# SparkFun_ZED-F9R_v11.net
KiCad netlist of a schematic drawn in EAGLE
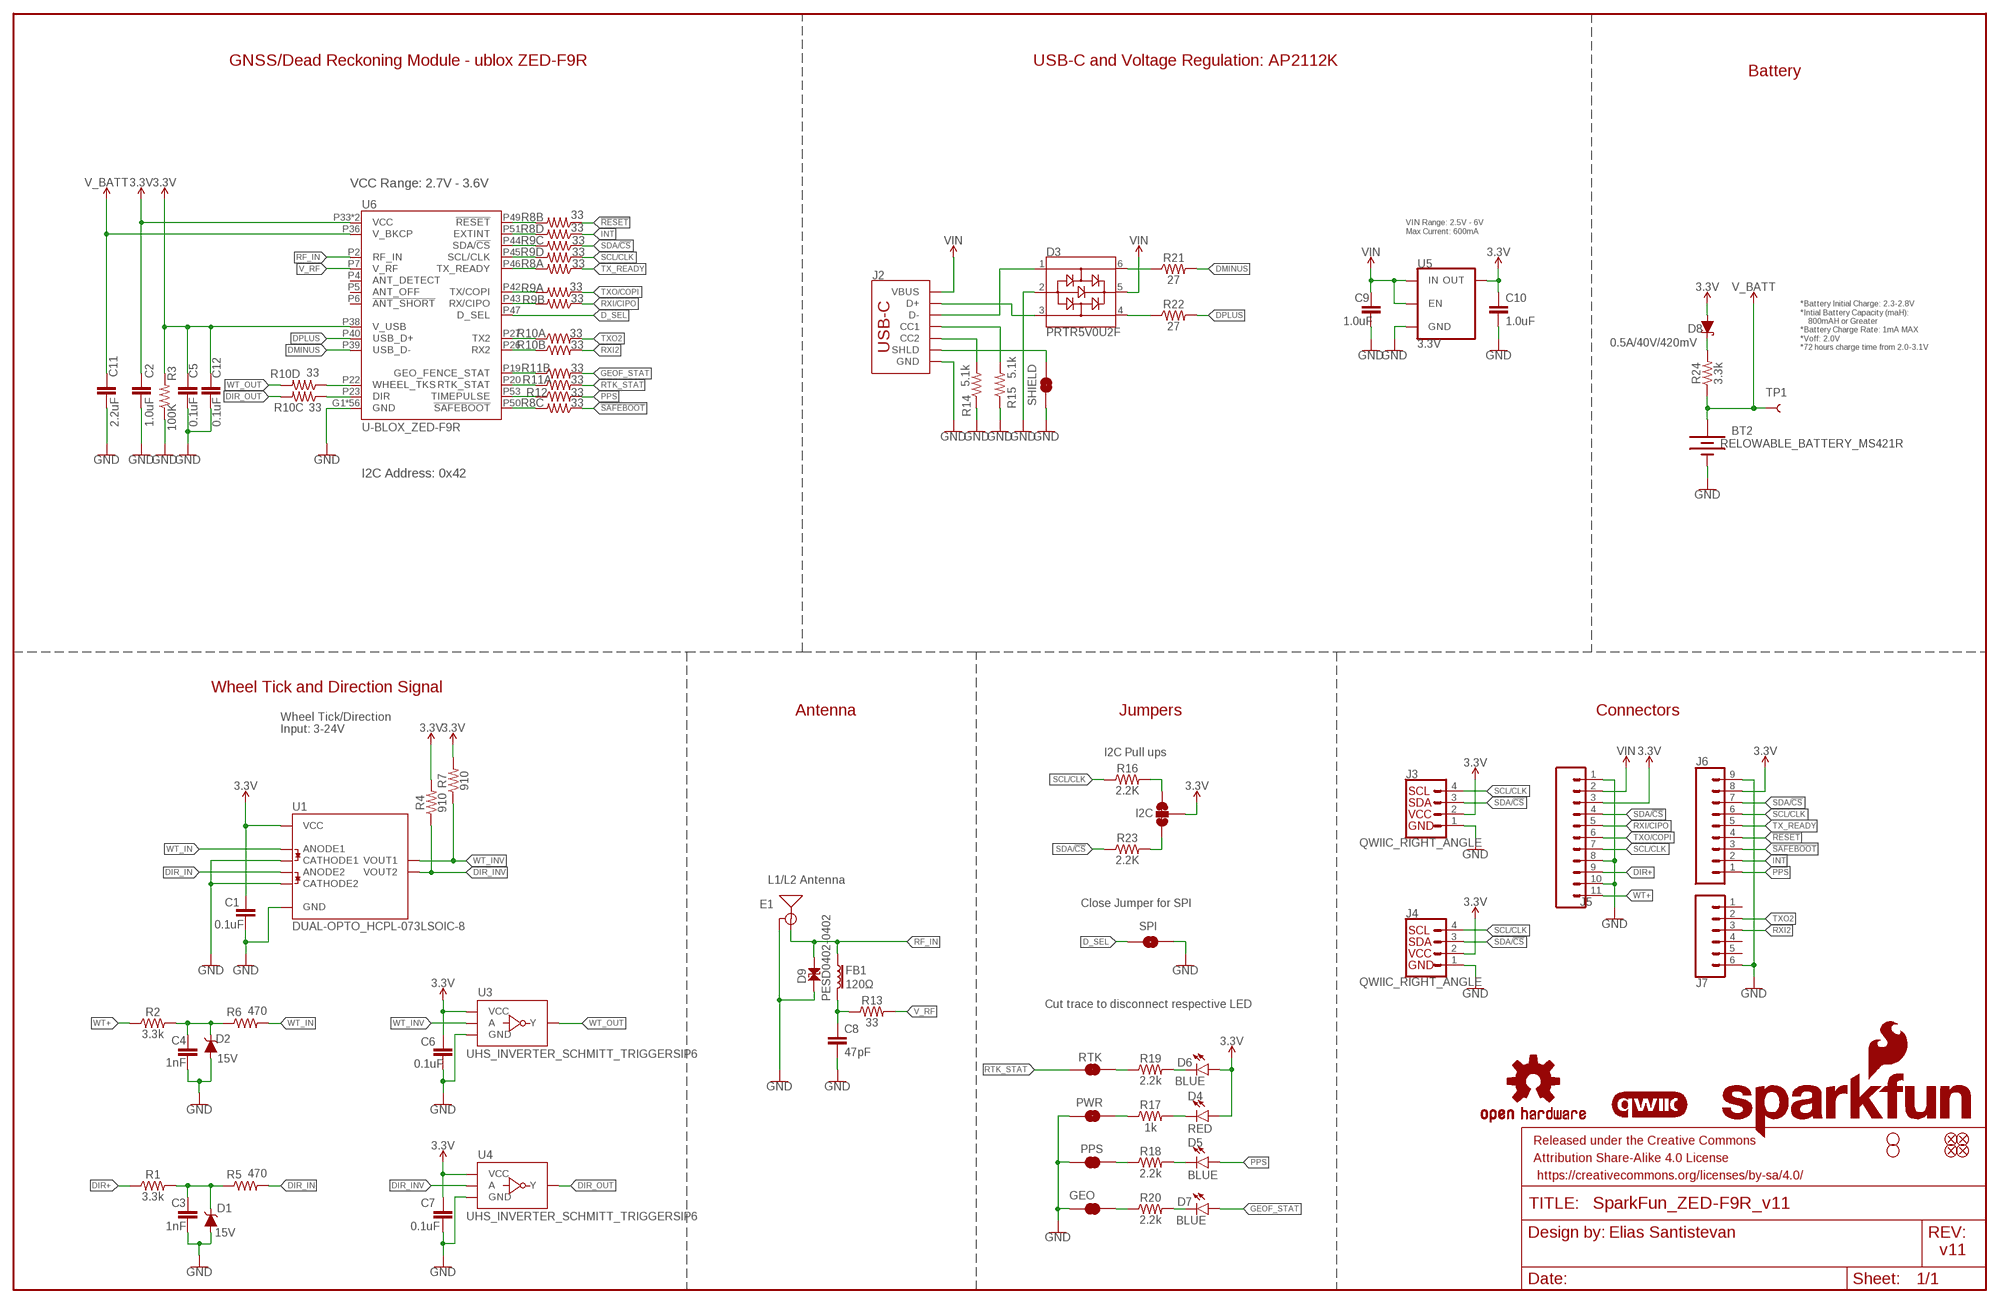
[diagram p0: schematic, sheet 1]

(export (version "E")
  (design (tool "Eeschema 10.0.6"))
  (components
    (comp (ref "$1_25_$_2020-03-30_22-52-05")
      (value "STAND-OFFTIGHT")
      (footprint "eagle-import:STAND-OFF-TIGHT")
      (libsource (lib "eagle-import") (part "STAND-OFFTIGHT"))
    )
    (comp (ref "BT2")
      (value "RELOWABLE_BATTERY_MS421R")
      (footprint "eagle-import:MS421R_IV03E")
      (libsource (lib "eagle-import") (part "RELOWABLE_BATTERY_MS421R"))
    )
    (comp (ref "C1")
      (value "0.1uF")
      (footprint "eagle-import:0402-TIGHT")
      (libsource (lib "eagle-import") (part "0.1UF-0402T-6.3V-10%-X7R"))
    )
    (comp (ref "C2")
      (value "1.0uF")
      (footprint "eagle-import:0402-TIGHT")
      (libsource (lib "eagle-import") (part "1.0UF-0402T-16V-10%"))
    )
    (comp (ref "C3")
      (value "1nF")
      (footprint "eagle-import:0402")
      (libsource (lib "eagle-import") (part "1.0NF/1000PF-0402-25V-10%-X7R"))
    )
    (comp (ref "C4")
      (value "1nF")
      (footprint "eagle-import:0402")
      (libsource (lib "eagle-import") (part "1.0NF/1000PF-0402-25V-10%-X7R"))
    )
    (comp (ref "C5")
      (value "0.1uF")
      (footprint "eagle-import:0402-TIGHT")
      (libsource (lib "eagle-import") (part "0.1UF-0402T-6.3V-10%-X7R"))
    )
    (comp (ref "C6")
      (value "0.1uF")
      (footprint "eagle-import:0402-TIGHT")
      (libsource (lib "eagle-import") (part "0.1UF-0402T-6.3V-10%-X7R"))
    )
    (comp (ref "C7")
      (value "0.1uF")
      (footprint "eagle-import:0402-TIGHT")
      (libsource (lib "eagle-import") (part "0.1UF-0402T-6.3V-10%-X7R"))
    )
    (comp (ref "C8")
      (value "47pF")
      (footprint "eagle-import:0402")
      (libsource (lib "eagle-import") (part "47PF-0402-25V-5%-X7R"))
    )
    (comp (ref "C9")
      (value "1.0uF")
      (footprint "eagle-import:0402-TIGHT")
      (libsource (lib "eagle-import") (part "1.0UF-0402T-16V-10%"))
    )
    (comp (ref "C10")
      (value "1.0uF")
      (footprint "eagle-import:0402-TIGHT")
      (libsource (lib "eagle-import") (part "1.0UF-0402T-16V-10%"))
    )
    (comp (ref "C11")
      (value "2.2uF")
      (footprint "eagle-import:0402-TIGHT")
      (libsource (lib "eagle-import") (part "2.2UF-0402_TIGHT-10V-10%-X5R"))
    )
    (comp (ref "C12")
      (value "0.1uF")
      (footprint "eagle-import:0402-TIGHT")
      (libsource (lib "eagle-import") (part "0.1UF-0402T-6.3V-10%-X7R"))
    )
    (comp (ref "D1")
      (value "15V")
      (footprint "eagle-import:SOT23-3")
      (libsource (lib "eagle-import") (part "DIODE-ZENER-BZX84C15LT3G"))
    )
    (comp (ref "D2")
      (value "15V")
      (footprint "eagle-import:SOT23-3")
      (libsource (lib "eagle-import") (part "DIODE-ZENER-BZX84C15LT3G"))
    )
    (comp (ref "D3")
      (value "PRTR5V0U2F")
      (footprint "eagle-import:SOT886")
      (libsource (lib "eagle-import") (part "PRTR5V0U2F"))
    )
    (comp (ref "D4")
      (value "RED")
      (footprint "eagle-import:LED-0603")
      (libsource (lib "eagle-import") (part "LED-RED0603"))
    )
    (comp (ref "D5")
      (value "BLUE")
      (footprint "eagle-import:LED-0603")
      (libsource (lib "eagle-import") (part "LED-BLUE0603"))
    )
    (comp (ref "D6")
      (value "BLUE")
      (footprint "eagle-import:LED-0603")
      (libsource (lib "eagle-import") (part "LED-BLUE0603"))
    )
    (comp (ref "D7")
      (value "BLUE")
      (footprint "eagle-import:LED-0603")
      (libsource (lib "eagle-import") (part "LED-BLUE0603"))
    )
    (comp (ref "D8")
      (value "0.5A/40V/420mV")
      (footprint "eagle-import:SOD-323")
      (libsource (lib "eagle-import") (part "DIODE-SCHOTTKY-PMEG4005EJ"))
    )
    (comp (ref "D9")
      (value "PESD0402-0402")
      (footprint "eagle-import:0402")
      (fields
        (field (name "DIGIKEY_PART") "PESD0402-140CT-ND")
        (field (name "MOUSE_PART") "650-PESD0402-140")
      )
      (libsource (lib "eagle-import") (part "PESD0402-0402"))
    )
    (comp (ref "E1")
      (value "ANTENNA-SMA-GROUNDEDEDGE_SMA")
      (footprint "eagle-import:SMA-EDGE")
      (libsource (lib "eagle-import") (part "ANTENNA-SMA-GROUNDEDEDGE_SMA"))
    )
    (comp (ref "FB1")
      (value "120Ω")
      (footprint "eagle-import:0402")
      (fields (field (name "MFG_PART") "BLM15HB121SN1D"))
      (libsource (lib "eagle-import") (part "FERRITE_BEAD-120_OHM-0402"))
    )
    (comp (ref "FD1")
      (value "FIDUCIALUFIDUCIAL")
      (footprint "eagle-import:FIDUCIAL-MICRO")
      (libsource (lib "eagle-import") (part "FIDUCIALUFIDUCIAL"))
    )
    (comp (ref "FD2")
      (value "FIDUCIALUFIDUCIAL")
      (footprint "eagle-import:FIDUCIAL-MICRO")
      (libsource (lib "eagle-import") (part "FIDUCIALUFIDUCIAL"))
    )
    (comp (ref "FD3")
      (value "FIDUCIALUFIDUCIAL")
      (footprint "eagle-import:FIDUCIAL-MICRO")
      (libsource (lib "eagle-import") (part "FIDUCIALUFIDUCIAL"))
    )
    (comp (ref "FD4")
      (value "FIDUCIALUFIDUCIAL")
      (footprint "eagle-import:FIDUCIAL-MICRO")
      (libsource (lib "eagle-import") (part "FIDUCIALUFIDUCIAL"))
    )
    (comp (ref "FRAME1")
      (value "FRAME-LEDGER")
      (footprint "eagle-import:CREATIVE_COMMONS")
      (libsource (lib "eagle-import") (part "FRAME-LEDGER"))
    )
    (comp (ref "GEO")
      (value "JUMPER-SMT_2_NC_TRACE_SILK")
      (footprint "eagle-import:SMT-JUMPER_2_NC_TRACE_SILK")
      (libsource (lib "eagle-import") (part "JUMPER-SMT_2_NC_TRACE_SILK"))
    )
    (comp (ref "H2")
      (value "STAND-OFFTIGHT")
      (footprint "eagle-import:STAND-OFF-TIGHT")
      (libsource (lib "eagle-import") (part "STAND-OFFTIGHT"))
    )
    (comp (ref "I2C")
      (value "JUMPER-SMT_3_2-NC_TRACE_SILK")
      (footprint "eagle-import:SMT-JUMPER_3_2-NC_TRACE_SILK")
      (libsource (lib "eagle-import") (part "JUMPER-SMT_3_2-NC_TRACE_SILK"))
    )
    (comp (ref "J2")
      (value "USB_C_2-LAYER_PADS")
      (footprint "eagle-import:USB-C-16P-2LAYER-PADS")
      (libsource (lib "eagle-import") (part "USB_C_2-LAYER_PADS"))
    )
    (comp (ref "J3")
      (value "QWIIC_RIGHT_ANGLE")
      (footprint "eagle-import:JST04_1MM_RA")
      (libsource (lib "eagle-import") (part "QWIIC_CONNECTORJS-1MM"))
    )
    (comp (ref "J4")
      (value "QWIIC_RIGHT_ANGLE")
      (footprint "eagle-import:JST04_1MM_RA")
      (libsource (lib "eagle-import") (part "QWIIC_CONNECTORJS-1MM"))
    )
    (comp (ref "J5")
      (value "CONN_111X11_NO_SILK")
      (footprint "eagle-import:1X11_NO_SILK")
      (libsource (lib "eagle-import") (part "CONN_111X11_NO_SILK"))
    )
    (comp (ref "J6")
      (value "CONN_09NO_SILK")
      (footprint "eagle-import:1X09_NO_SILK")
      (libsource (lib "eagle-import") (part "CONN_09NO_SILK"))
    )
    (comp (ref "J7")
      (value "CONN_06NO_SILK_NO_POP")
      (footprint "eagle-import:1X06_NO_SILK")
      (libsource (lib "eagle-import") (part "CONN_06NO_SILK_NO_POP"))
    )
    (comp (ref "LOGO1")
      (value "OSHW-LOGOS")
      (footprint "eagle-import:OSHW-LOGO-S")
      (libsource (lib "eagle-import") (part "OSHW-LOGOS"))
    )
    (comp (ref "LOGO2")
      (value "QWIIC_LOGO_4MM")
      (footprint "eagle-import:QWIIC_4MM")
      (libsource (lib "eagle-import") (part "QWIIC_LOGO_4MM"))
    )
    (comp (ref "LOGO3")
      (value "SFE_LOGO_NAME_FLAME.2_INCH")
      (footprint "eagle-import:SFE_LOGO_NAME_FLAME_.2")
      (libsource (lib "eagle-import") (part "SFE_LOGO_NAME_FLAME.2_INCH"))
    )
    (comp (ref "PPS")
      (value "JUMPER-SMT_2_NC_TRACE_SILK")
      (footprint "eagle-import:SMT-JUMPER_2_NC_TRACE_SILK")
      (libsource (lib "eagle-import") (part "JUMPER-SMT_2_NC_TRACE_SILK"))
    )
    (comp (ref "PWR")
      (value "JUMPER-SMT_2_NC_TRACE_SILK")
      (footprint "eagle-import:SMT-JUMPER_2_NC_TRACE_SILK")
      (libsource (lib "eagle-import") (part "JUMPER-SMT_2_NC_TRACE_SILK"))
    )
    (comp (ref "R1")
      (value "3.3k")
      (footprint "eagle-import:0603")
      (libsource (lib "eagle-import") (part "3.3KOHM-0603-1/10W-1%"))
    )
    (comp (ref "R2")
      (value "3.3k")
      (footprint "eagle-import:0603")
      (libsource (lib "eagle-import") (part "3.3KOHM-0603-1/10W-1%"))
    )
    (comp (ref "R3")
      (value "100K")
      (footprint "eagle-import:0402")
      (libsource (lib "eagle-import") (part "100KOHM-0402-1/16W-1%"))
    )
    (comp (ref "R4")
      (value "910")
      (footprint "eagle-import:0603")
      (libsource (lib "eagle-import") (part "910OHM-0603-1/10W-5%"))
    )
    (comp (ref "R5")
      (value "470")
      (footprint "eagle-import:0603")
      (libsource (lib "eagle-import") (part "470OHM-0603-1/10W-1%"))
    )
    (comp (ref "R6")
      (value "470")
      (footprint "eagle-import:0603")
      (libsource (lib "eagle-import") (part "470OHM-0603-1/10W-1%"))
    )
    (comp (ref "R7")
      (value "910")
      (footprint "eagle-import:0603")
      (libsource (lib "eagle-import") (part "910OHM-0603-1/10W-5%"))
    )
    (comp (ref "R8")
      (value "33")
      (footprint "eagle-import:1206_RA")
      (libsource (lib "eagle-import") (part "33OHM_RA-1206-1/16W-5%"))
    )
    (comp (ref "R9")
      (value "33")
      (footprint "eagle-import:1206_RA")
      (libsource (lib "eagle-import") (part "33OHM_RA-1206-1/16W-5%"))
    )
    (comp (ref "R10")
      (value "33")
      (footprint "eagle-import:1206_RA")
      (libsource (lib "eagle-import") (part "33OHM_RA-1206-1/16W-5%"))
    )
    (comp (ref "R11")
      (value "33")
      (footprint "eagle-import:1206_RA")
      (libsource (lib "eagle-import") (part "33OHM_RA-1206-1/16W-5%"))
    )
    (comp (ref "R12")
      (value "33")
      (footprint "eagle-import:0603")
      (libsource (lib "eagle-import") (part "33OHM-0603-1/10W-1%"))
    )
    (comp (ref "R13")
      (value "33")
      (footprint "eagle-import:0603")
      (libsource (lib "eagle-import") (part "33OHM-0603-1/10W-1%"))
    )
    (comp (ref "R14")
      (value "5.1k")
      (footprint "eagle-import:0402")
      (libsource (lib "eagle-import") (part "5.1KOHM-0402-1/16W-1%"))
    )
    (comp (ref "R15")
      (value "5.1k")
      (footprint "eagle-import:0402")
      (libsource (lib "eagle-import") (part "5.1KOHM-0402-1/16W-1%"))
    )
    (comp (ref "R16")
      (value "2.2K")
      (footprint "eagle-import:0402")
      (libsource (lib "eagle-import") (part "2.2KOHM-0402-1/16W-1%"))
    )
    (comp (ref "R17")
      (value "1KOHM-0402-1/16W-1%")
      (footprint "eagle-import:0402")
      (libsource (lib "eagle-import") (part "1KOHM-0402-1/16W-1%"))
    )
    (comp (ref "R18")
      (value "2.2k")
      (footprint "eagle-import:0603")
      (libsource (lib "eagle-import") (part "2.2KOHM-0603-1/10W-1%"))
    )
    (comp (ref "R19")
      (value "2.2k")
      (footprint "eagle-import:0603")
      (libsource (lib "eagle-import") (part "2.2KOHM-0603-1/10W-1%"))
    )
    (comp (ref "R20")
      (value "2.2k")
      (footprint "eagle-import:0603")
      (libsource (lib "eagle-import") (part "2.2KOHM-0603-1/10W-1%"))
    )
    (comp (ref "R21")
      (value "27")
      (footprint "eagle-import:0603")
      (libsource (lib "eagle-import") (part "27OHM-0603-1/10W-1%"))
    )
    (comp (ref "R22")
      (value "27")
      (footprint "eagle-import:0603")
      (libsource (lib "eagle-import") (part "27OHM-0603-1/10W-1%"))
    )
    (comp (ref "R23")
      (value "2.2K")
      (footprint "eagle-import:0402")
      (libsource (lib "eagle-import") (part "2.2KOHM-0402-1/16W-1%"))
    )
    (comp (ref "R24")
      (value "3.3k")
      (footprint "eagle-import:0603")
      (libsource (lib "eagle-import") (part "3.3KOHM-0603-1/10W-1%"))
    )
    (comp (ref "RTK")
      (value "JUMPER-SMT_2_NC_TRACE_SILK")
      (footprint "eagle-import:SMT-JUMPER_2_NC_TRACE_SILK")
      (libsource (lib "eagle-import") (part "JUMPER-SMT_2_NC_TRACE_SILK"))
    )
    (comp (ref "SHIELD")
      (value "JUMPER-SMT_2_NC_TRACE_SILK")
      (footprint "eagle-import:SMT-JUMPER_2_NC_TRACE_SILK")
      (libsource (lib "eagle-import") (part "JUMPER-SMT_2_NC_TRACE_SILK"))
    )
    (comp (ref "SPI")
      (value "JUMPER-SMT_2_NO_SILK")
      (footprint "eagle-import:SMT-JUMPER_2_NO_SILK")
      (libsource (lib "eagle-import") (part "JUMPER-SMT_2_NO_SILK"))
    )
    (comp (ref "TP1")
      (value "TEST-POINT3X5")
      (footprint "eagle-import:PAD.03X.05")
      (libsource (lib "eagle-import") (part "TEST-POINT3X5"))
    )
    (comp (ref "U1")
      (value "DUAL-OPTO_HCPL-073LSOIC-8")
      (footprint "eagle-import:SO08")
      (libsource (lib "eagle-import") (part "DUAL-OPTO_HCPL-073LSOIC-8"))
    )
    (comp (ref "U3")
      (value "UHS_INVERTER_SCHMITT_TRIGGERSIP6")
      (footprint "eagle-import:SIP6_MICROPAK2")
      (libsource (lib "eagle-import") (part "UHS_INVERTER_SCHMITT_TRIGGER_MPAK2"))
    )
    (comp (ref "U4")
      (value "UHS_INVERTER_SCHMITT_TRIGGERSIP6")
      (footprint "eagle-import:SIP6_MICROPAK2")
      (libsource (lib "eagle-import") (part "UHS_INVERTER_SCHMITT_TRIGGER_MPAK2"))
    )
    (comp (ref "U5")
      (value "3.3V")
      (footprint "eagle-import:SOT23-5")
      (libsource (lib "eagle-import") (part "V_REG_AP2112K-3.3V"))
    )
    (comp (ref "U6")
      (value "U-BLOX_ZED-F9R")
      (footprint "eagle-import:UBLOX_ZED_F9R")
      (libsource (lib "eagle-import") (part "U-BLOX_ZED-F9R"))
    )
  )
  (nets
    (net (code "1") (name "/SDA{slash}~{CS}") (class "Default")
      (node (ref "J3") (pin "3") (pinfunction "3_3") (pintype "passive"))
      (node (ref "J4") (pin "3") (pinfunction "3_3") (pintype "passive"))
      (node (ref "J5") (pin "4") (pinfunction "4_4") (pintype "passive"))
      (node (ref "J6") (pin "7") (pinfunction "7_7") (pintype "passive"))
      (node (ref "R23") (pin "1") (pinfunction "1_1") (pintype "passive"))
      (node (ref "R9") (pin "P3") (pinfunction "1_P3") (pintype "passive"))
    )
    (net (code "2") (name "/~{RESET}") (class "Default")
      (node (ref "J6") (pin "4") (pinfunction "4_4") (pintype "passive"))
      (node (ref "R8") (pin "P2") (pinfunction "1_P2") (pintype "passive"))
    )
    (net (code "3") (name "/~{SAFEBOOT}") (class "Default")
      (node (ref "J6") (pin "3") (pinfunction "3_3") (pintype "passive"))
      (node (ref "R8") (pin "P3") (pinfunction "1_P3") (pintype "passive"))
    )
    (net (code "4") (name "3.3V") (class "Default")
      (node (ref "C1") (pin "1") (pinfunction "1_1") (pintype "passive"))
      (node (ref "C10") (pin "1") (pinfunction "1_1") (pintype "passive"))
      (node (ref "C12") (pin "1") (pinfunction "1_1") (pintype "passive"))
      (node (ref "C2") (pin "1") (pinfunction "1_1") (pintype "passive"))
      (node (ref "C5") (pin "1") (pinfunction "1_1") (pintype "passive"))
      (node (ref "C6") (pin "1") (pinfunction "1_1") (pintype "passive"))
      (node (ref "C7") (pin "1") (pinfunction "1_1") (pintype "passive"))
      (node (ref "D4") (pin "A") (pinfunction "A_A") (pintype "passive"))
      (node (ref "D6") (pin "A") (pinfunction "A_A") (pintype "passive"))
      (node (ref "D8") (pin "A") (pinfunction "A_A") (pintype "passive"))
      (node (ref "I2C") (pin "2") (pinfunction "2_2") (pintype "passive"))
      (node (ref "J3") (pin "2") (pinfunction "2_2") (pintype "power_in"))
      (node (ref "J4") (pin "2") (pinfunction "2_2") (pintype "power_in"))
      (node (ref "J5") (pin "3") (pinfunction "3_3") (pintype "passive"))
      (node (ref "J6") (pin "8") (pinfunction "8_8") (pintype "passive"))
      (node (ref "R3") (pin "2") (pinfunction "2_2") (pintype "passive"))
      (node (ref "R4") (pin "2") (pinfunction "2_2") (pintype "passive"))
      (node (ref "R7") (pin "2") (pinfunction "2_2") (pintype "passive"))
      (node (ref "U1") (pin "8") (pinfunction "VCC_8") (pintype "power_in"))
      (node (ref "U3") (pin "P6") (pinfunction "VCC_P6") (pintype "power_in"))
      (node (ref "U4") (pin "P6") (pinfunction "VCC_P6") (pintype "power_in"))
      (node (ref "U5") (pin "5") (pinfunction "OUT_5") (pintype "passive"))
      (node (ref "U6") (pin "P33") (pinfunction "VCC_P33") (pintype "power_in"))
      (node (ref "U6") (pin "P34") (pinfunction "VCC_P34") (pintype "power_in"))
      (node (ref "U6") (pin "P38") (pinfunction "V_USB_P38") (pintype "power_in"))
    )
    (net (code "5") (name "DIR+") (class "Default")
      (node (ref "J5") (pin "9") (pinfunction "9_9") (pintype "passive"))
      (node (ref "R1") (pin "1") (pinfunction "1_1") (pintype "passive"))
    )
    (net (code "6") (name "DIR_IN") (class "Default")
      (node (ref "R5") (pin "2") (pinfunction "2_2") (pintype "passive"))
      (node (ref "U1") (pin "4") (pinfunction "ANODE2_4") (pintype "input"))
    )
    (net (code "7") (name "DIR_INV") (class "Default")
      (node (ref "R4") (pin "1") (pinfunction "1_1") (pintype "passive"))
      (node (ref "U1") (pin "6") (pinfunction "VOUT2_6") (pintype "output"))
      (node (ref "U4") (pin "P2") (pinfunction "A_P2") (pintype "input"))
    )
    (net (code "8") (name "DIR_OUT") (class "Default")
      (node (ref "R10") (pin "P6") (pinfunction "2_P6") (pintype "passive"))
      (node (ref "U4") (pin "P4") (pinfunction "Y_P4") (pintype "output"))
    )
    (net (code "9") (name "DMINUS") (class "Default")
      (node (ref "R21") (pin "2") (pinfunction "2_2") (pintype "passive"))
      (node (ref "U6") (pin "P39") (pinfunction "USB_D-_P39") (pintype "bidirectional"))
    )
    (net (code "10") (name "DPLUS") (class "Default")
      (node (ref "R22") (pin "2") (pinfunction "2_2") (pintype "passive"))
      (node (ref "U6") (pin "P40") (pinfunction "USB_D+_P40") (pintype "bidirectional"))
    )
    (net (code "11") (name "D_SEL") (class "Default")
      (node (ref "SPI") (pin "1") (pinfunction "1_1") (pintype "passive"))
      (node (ref "U6") (pin "P47") (pinfunction "D_SEL_P47") (pintype "bidirectional"))
    )
    (net (code "12") (name "GEOF_STAT") (class "Default")
      (node (ref "D7") (pin "A") (pinfunction "A_A") (pintype "passive"))
      (node (ref "R11") (pin "P7") (pinfunction "2_P7") (pintype "passive"))
    )
    (net (code "13") (name "GND") (class "Default")
      (node (ref "BT2") (pin "-") (pinfunction "-_-") (pintype "power_in"))
      (node (ref "C1") (pin "2") (pinfunction "2_2") (pintype "passive"))
      (node (ref "C10") (pin "2") (pinfunction "2_2") (pintype "passive"))
      (node (ref "C11") (pin "2") (pinfunction "2_2") (pintype "passive"))
      (node (ref "C12") (pin "2") (pinfunction "2_2") (pintype "passive"))
      (node (ref "C2") (pin "2") (pinfunction "2_2") (pintype "passive"))
      (node (ref "C3") (pin "2") (pinfunction "2_2") (pintype "passive"))
      (node (ref "C4") (pin "2") (pinfunction "2_2") (pintype "passive"))
      (node (ref "C5") (pin "2") (pinfunction "2_2") (pintype "passive"))
      (node (ref "C6") (pin "2") (pinfunction "2_2") (pintype "passive"))
      (node (ref "C7") (pin "2") (pinfunction "2_2") (pintype "passive"))
      (node (ref "C8") (pin "2") (pinfunction "2_2") (pintype "passive"))
      (node (ref "C9") (pin "2") (pinfunction "2_2") (pintype "passive"))
      (node (ref "D1") (pin "1") (pinfunction "A_1") (pintype "passive"))
      (node (ref "D2") (pin "1") (pinfunction "A_1") (pintype "passive"))
      (node (ref "D3") (pin "2") (pinfunction "2_2") (pintype "power_in"))
      (node (ref "D9") (pin "1") (pinfunction "1_1") (pintype "bidirectional"))
      (node (ref "E1") (pin "GND@0") (pinfunction "GND_GND@0") (pintype "bidirectional"))
      (node (ref "E1") (pin "GND@1") (pinfunction "GND_GND@1") (pintype "bidirectional"))
      (node (ref "E1") (pin "GND@2") (pinfunction "GND_GND@2") (pintype "bidirectional"))
      (node (ref "E1") (pin "GND@3") (pinfunction "GND_GND@3") (pintype "bidirectional"))
      (node (ref "GEO") (pin "1") (pinfunction "1_1") (pintype "passive"))
      (node (ref "J2") (pin "GND") (pinfunction "GND_GND") (pintype "bidirectional"))
      (node (ref "J2") (pin "GND2") (pinfunction "GND_GND2") (pintype "bidirectional"))
      (node (ref "J3") (pin "1") (pinfunction "1_1") (pintype "power_in"))
      (node (ref "J4") (pin "1") (pinfunction "1_1") (pintype "power_in"))
      (node (ref "J5") (pin "1") (pinfunction "1_1") (pintype "passive"))
      (node (ref "J5") (pin "10") (pinfunction "10_10") (pintype "passive"))
      (node (ref "J5") (pin "8") (pinfunction "8_8") (pintype "passive"))
      (node (ref "J6") (pin "9") (pinfunction "9_9") (pintype "passive"))
      (node (ref "J7") (pin "6") (pinfunction "6_6") (pintype "passive"))
      (node (ref "PPS") (pin "1") (pinfunction "1_1") (pintype "passive"))
      (node (ref "PWR") (pin "1") (pinfunction "1_1") (pintype "passive"))
      (node (ref "R14") (pin "1") (pinfunction "1_1") (pintype "passive"))
      (node (ref "R15") (pin "1") (pinfunction "1_1") (pintype "passive"))
      (node (ref "R3") (pin "1") (pinfunction "1_1") (pintype "passive"))
      (node (ref "SHIELD") (pin "1") (pinfunction "1_1") (pintype "passive"))
      (node (ref "SPI") (pin "2") (pinfunction "2_2") (pintype "passive"))
      (node (ref "U1") (pin "2") (pinfunction "CATHODE1_2") (pintype "input"))
      (node (ref "U1") (pin "3") (pinfunction "CATHODE2_3") (pintype "input"))
      (node (ref "U1") (pin "5") (pinfunction "GND_5") (pintype "power_in"))
      (node (ref "U3") (pin "P3") (pinfunction "GND_P3") (pintype "power_in"))
      (node (ref "U4") (pin "P3") (pinfunction "GND_P3") (pintype "power_in"))
      (node (ref "U5") (pin "2") (pinfunction "GND_2") (pintype "input"))
      (node (ref "U6") (pin "G1") (pinfunction "GND_G1") (pintype "power_in"))
      (node (ref "U6") (pin "G10") (pinfunction "GND_G10") (pintype "power_in"))
      (node (ref "U6") (pin "G11") (pinfunction "GND_G11") (pintype "power_in"))
      (node (ref "U6") (pin "G12") (pinfunction "GND_G12") (pintype "power_in"))
      (node (ref "U6") (pin "G13") (pinfunction "GND_G13") (pintype "power_in"))
      (node (ref "U6") (pin "G14") (pinfunction "GND_G14") (pintype "power_in"))
      (node (ref "U6") (pin "G15") (pinfunction "GND_G15") (pintype "power_in"))
      (node (ref "U6") (pin "G16") (pinfunction "GND_G16") (pintype "power_in"))
      (node (ref "U6") (pin "G17") (pinfunction "GND_G17") (pintype "power_in"))
      (node (ref "U6") (pin "G18") (pinfunction "GND_G18") (pintype "power_in"))
      (node (ref "U6") (pin "G19") (pinfunction "GND_G19") (pintype "power_in"))
      (node (ref "U6") (pin "G2") (pinfunction "GND_G2") (pintype "power_in"))
      (node (ref "U6") (pin "G20") (pinfunction "GND_G20") (pintype "power_in"))
      (node (ref "U6") (pin "G21") (pinfunction "GND_G21") (pintype "power_in"))
      (node (ref "U6") (pin "G22") (pinfunction "GND_G22") (pintype "power_in"))
      (node (ref "U6") (pin "G23") (pinfunction "GND_G23") (pintype "power_in"))
      (node (ref "U6") (pin "G24") (pinfunction "GND_G24") (pintype "power_in"))
      (node (ref "U6") (pin "G25") (pinfunction "GND_G25") (pintype "power_in"))
      (node (ref "U6") (pin "G26") (pinfunction "GND_G26") (pintype "power_in"))
      (node (ref "U6") (pin "G27") (pinfunction "GND_G27") (pintype "power_in"))
      (node (ref "U6") (pin "G28") (pinfunction "GND_G28") (pintype "power_in"))
      (node (ref "U6") (pin "G29") (pinfunction "GND_G29") (pintype "power_in"))
      (node (ref "U6") (pin "G3") (pinfunction "GND_G3") (pintype "power_in"))
      (node (ref "U6") (pin "G30") (pinfunction "GND_G30") (pintype "power_in"))
      (node (ref "U6") (pin "G31") (pinfunction "GND_G31") (pintype "power_in"))
      (node (ref "U6") (pin "G32") (pinfunction "GND_G32") (pintype "power_in"))
      (node (ref "U6") (pin "G33") (pinfunction "GND_G33") (pintype "power_in"))
      (node (ref "U6") (pin "G34") (pinfunction "GND_G34") (pintype "power_in"))
      (node (ref "U6") (pin "G35") (pinfunction "GND_G35") (pintype "power_in"))
      (node (ref "U6") (pin "G36") (pinfunction "GND_G36") (pintype "power_in"))
      (node (ref "U6") (pin "G37") (pinfunction "GND_G37") (pintype "power_in"))
      (node (ref "U6") (pin "G38") (pinfunction "GND_G38") (pintype "power_in"))
      (node (ref "U6") (pin "G39") (pinfunction "GND_G39") (pintype "power_in"))
      (node (ref "U6") (pin "G4") (pinfunction "GND_G4") (pintype "power_in"))
      (node (ref "U6") (pin "G40") (pinfunction "GND_G40") (pintype "power_in"))
      (node (ref "U6") (pin "G41") (pinfunction "GND_G41") (pintype "power_in"))
      (node (ref "U6") (pin "G42") (pinfunction "GND_G42") (pintype "power_in"))
      (node (ref "U6") (pin "G43") (pinfunction "GND_G43") (pintype "power_in"))
      (node (ref "U6") (pin "G44") (pinfunction "GND_G44") (pintype "power_in"))
      (node (ref "U6") (pin "G45") (pinfunction "GND_G45") (pintype "power_in"))
      (node (ref "U6") (pin "G46") (pinfunction "GND_G46") (pintype "power_in"))
      (node (ref "U6") (pin "G47") (pinfunction "GND_G47") (pintype "power_in"))
      (node (ref "U6") (pin "G48") (pinfunction "GND_G48") (pintype "power_in"))
      (node (ref "U6") (pin "G5") (pinfunction "GND_G5") (pintype "power_in"))
      (node (ref "U6") (pin "G6") (pinfunction "GND_G6") (pintype "power_in"))
      (node (ref "U6") (pin "G7") (pinfunction "GND_G7") (pintype "power_in"))
      (node (ref "U6") (pin "G8") (pinfunction "GND_G8") (pintype "power_in"))
      (node (ref "U6") (pin "G9") (pinfunction "GND_G9") (pintype "power_in"))
      (node (ref "U6") (pin "P1") (pinfunction "GND_P1") (pintype "power_in"))
      (node (ref "U6") (pin "P12") (pinfunction "GND_P12") (pintype "power_in"))
      (node (ref "U6") (pin "P14") (pinfunction "GND_P14") (pintype "power_in"))
      (node (ref "U6") (pin "P3") (pinfunction "GND_P3") (pintype "power_in"))
      (node (ref "U6") (pin "P32") (pinfunction "GND_P32") (pintype "power_in"))
      (node (ref "U6") (pin "P37") (pinfunction "GND_P37") (pintype "power_in"))
      (node (ref "U6") (pin "P41") (pinfunction "GND_P41") (pintype "power_in"))
      (node (ref "U6") (pin "P48") (pinfunction "GND_P48") (pintype "power_in"))
    )
    (net (code "14") (name "INT") (class "Default")
      (node (ref "J6") (pin "2") (pinfunction "2_2") (pintype "passive"))
      (node (ref "R8") (pin "P4") (pinfunction "1_P4") (pintype "passive"))
    )
    (net (code "15") (name "Net-(C8-Pad1)") (class "Default")
      (node (ref "C8") (pin "1") (pinfunction "1_1") (pintype "passive"))
      (node (ref "FB1") (pin "2") (pinfunction "2_2") (pintype "passive"))
      (node (ref "R13") (pin "1") (pinfunction "1_1") (pintype "passive"))
    )
    (net (code "16") (name "Net-(D1-C)") (class "Default")
      (node (ref "C3") (pin "1") (pinfunction "1_1") (pintype "passive"))
      (node (ref "D1") (pin "3") (pinfunction "C_3") (pintype "passive"))
      (node (ref "R1") (pin "2") (pinfunction "2_2") (pintype "passive"))
      (node (ref "R5") (pin "1") (pinfunction "1_1") (pintype "passive"))
    )
    (net (code "17") (name "Net-(D2-C)") (class "Default")
      (node (ref "C4") (pin "1") (pinfunction "1_1") (pintype "passive"))
      (node (ref "D2") (pin "3") (pinfunction "C_3") (pintype "passive"))
      (node (ref "R2") (pin "2") (pinfunction "2_2") (pintype "passive"))
      (node (ref "R6") (pin "1") (pinfunction "1_1") (pintype "passive"))
    )
    (net (code "18") (name "Net-(D3-Pad1)") (class "Default")
      (node (ref "D3") (pin "1") (pinfunction "1_1") (pintype "bidirectional"))
      (node (ref "J2") (pin "A7") (pinfunction "D-_A7") (pintype "bidirectional"))
      (node (ref "J2") (pin "B7") (pinfunction "D-_B7") (pintype "bidirectional"))
    )
    (net (code "19") (name "Net-(D3-Pad3)") (class "Default")
      (node (ref "D3") (pin "3") (pinfunction "3_3") (pintype "bidirectional"))
      (node (ref "J2") (pin "A6") (pinfunction "D+_A6") (pintype "bidirectional"))
      (node (ref "J2") (pin "B6") (pinfunction "D+_B6") (pintype "bidirectional"))
    )
    (net (code "20") (name "Net-(D3-Pad4)") (class "Default")
      (node (ref "D3") (pin "4") (pinfunction "4_4") (pintype "bidirectional"))
      (node (ref "R22") (pin "1") (pinfunction "1_1") (pintype "passive"))
    )
    (net (code "21") (name "Net-(D3-Pad6)") (class "Default")
      (node (ref "D3") (pin "6") (pinfunction "6_6") (pintype "bidirectional"))
      (node (ref "R21") (pin "1") (pinfunction "1_1") (pintype "passive"))
    )
    (net (code "22") (name "Net-(D4-PadC)") (class "Default")
      (node (ref "D4") (pin "C") (pinfunction "C_C") (pintype "passive"))
      (node (ref "R17") (pin "2") (pinfunction "2_2") (pintype "passive"))
    )
    (net (code "23") (name "Net-(D5-PadC)") (class "Default")
      (node (ref "D5") (pin "C") (pinfunction "C_C") (pintype "passive"))
      (node (ref "R18") (pin "2") (pinfunction "2_2") (pintype "passive"))
    )
    (net (code "24") (name "Net-(D6-PadC)") (class "Default")
      (node (ref "D6") (pin "C") (pinfunction "C_C") (pintype "passive"))
      (node (ref "R19") (pin "2") (pinfunction "2_2") (pintype "passive"))
    )
    (net (code "25") (name "Net-(D7-PadC)") (class "Default")
      (node (ref "D7") (pin "C") (pinfunction "C_C") (pintype "passive"))
      (node (ref "R20") (pin "2") (pinfunction "2_2") (pintype "passive"))
    )
    (net (code "26") (name "Net-(D8-PadC)") (class "Default")
      (node (ref "D8") (pin "C") (pinfunction "C_C") (pintype "passive"))
      (node (ref "R24") (pin "2") (pinfunction "2_2") (pintype "passive"))
    )
    (net (code "27") (name "Net-(GEO-Pad2)") (class "Default")
      (node (ref "GEO") (pin "2") (pinfunction "2_2") (pintype "passive"))
      (node (ref "R20") (pin "1") (pinfunction "1_1") (pintype "passive"))
    )
    (net (code "28") (name "Net-(I2C-Pad1)") (class "Default")
      (node (ref "I2C") (pin "1") (pinfunction "1_1") (pintype "passive"))
      (node (ref "R23") (pin "2") (pinfunction "2_2") (pintype "passive"))
    )
    (net (code "29") (name "Net-(I2C-Pad3)") (class "Default")
      (node (ref "I2C") (pin "3") (pinfunction "3_3") (pintype "passive"))
      (node (ref "R16") (pin "2") (pinfunction "2_2") (pintype "passive"))
    )
    (net (code "30") (name "Net-(J2-CC1)") (class "Default")
      (node (ref "J2") (pin "A5") (pinfunction "CC1_A5") (pintype "bidirectional"))
      (node (ref "R15") (pin "2") (pinfunction "2_2") (pintype "passive"))
    )
    (net (code "31") (name "Net-(J2-CC2)") (class "Default")
      (node (ref "J2") (pin "B5") (pinfunction "CC2_B5") (pintype "bidirectional"))
      (node (ref "R14") (pin "2") (pinfunction "2_2") (pintype "passive"))
    )
    (net (code "32") (name "Net-(J2-SHLD-PadSHLD1)") (class "Default")
      (node (ref "J2") (pin "SHLD1") (pinfunction "SHLD_SHLD1") (pintype "bidirectional"))
      (node (ref "J2") (pin "SHLD2") (pinfunction "SHLD_SHLD2") (pintype "bidirectional"))
      (node (ref "J2") (pin "SHLD3") (pinfunction "SHLD_SHLD3") (pintype "bidirectional"))
      (node (ref "J2") (pin "SHLD4") (pinfunction "SHLD_SHLD4") (pintype "bidirectional"))
      (node (ref "SHIELD") (pin "2") (pinfunction "2_2") (pintype "passive"))
    )
    (net (code "33") (name "Net-(PPS-Pad2)") (class "Default")
      (node (ref "PPS") (pin "2") (pinfunction "2_2") (pintype "passive"))
      (node (ref "R18") (pin "1") (pinfunction "1_1") (pintype "passive"))
    )
    (net (code "34") (name "Net-(PWR-Pad2)") (class "Default")
      (node (ref "PWR") (pin "2") (pinfunction "2_2") (pintype "passive"))
      (node (ref "R17") (pin "1") (pinfunction "1_1") (pintype "passive"))
    )
    (net (code "35") (name "Net-(R8A-2)") (class "Default")
      (node (ref "R8") (pin "P8") (pinfunction "2_P8") (pintype "passive"))
      (node (ref "U6") (pin "P46") (pinfunction "TX_READY_P46") (pintype "bidirectional"))
    )
    (net (code "36") (name "Net-(R8B-2)") (class "Default")
      (node (ref "R8") (pin "P7") (pinfunction "2_P7") (pintype "passive"))
      (node (ref "U6") (pin "P49") (pinfunction "~{RESET}_P49") (pintype "bidirectional"))
    )
    (net (code "37") (name "Net-(R8C-2)") (class "Default")
      (node (ref "R8") (pin "P6") (pinfunction "2_P6") (pintype "passive"))
      (node (ref "U6") (pin "P50") (pinfunction "~{SAFEBOOT}_P50") (pintype "input"))
    )
    (net (code "38") (name "Net-(R8D-2)") (class "Default")
      (node (ref "R8") (pin "P5") (pinfunction "2_P5") (pintype "passive"))
      (node (ref "U6") (pin "P51") (pinfunction "EXTINT_P51") (pintype "bidirectional"))
    )
    (net (code "39") (name "Net-(R9A-2)") (class "Default")
      (node (ref "R9") (pin "P8") (pinfunction "2_P8") (pintype "passive"))
      (node (ref "U6") (pin "P42") (pinfunction "TX/COPI_P42") (pintype "bidirectional"))
    )
    (net (code "40") (name "Net-(R9B-2)") (class "Default")
      (node (ref "R9") (pin "P7") (pinfunction "2_P7") (pintype "passive"))
      (node (ref "U6") (pin "P43") (pinfunction "RX/CIPO_P43") (pintype "bidirectional"))
    )
    (net (code "41") (name "Net-(R9C-2)") (class "Default")
      (node (ref "R9") (pin "P6") (pinfunction "2_P6") (pintype "passive"))
      (node (ref "U6") (pin "P44") (pinfunction "SDA/~{CS}_P44") (pintype "bidirectional"))
    )
    (net (code "42") (name "Net-(R9D-2)") (class "Default")
      (node (ref "R9") (pin "P5") (pinfunction "2_P5") (pintype "passive"))
      (node (ref "U6") (pin "P45") (pinfunction "SCL/CLK_P45") (pintype "bidirectional"))
    )
    (net (code "43") (name "Net-(R10A-1)") (class "Default")
      (node (ref "R10") (pin "P1") (pinfunction "1_P1") (pintype "passive"))
      (node (ref "U6") (pin "P27") (pinfunction "TX2_P27") (pintype "output"))
    )
    (net (code "44") (name "Net-(R10B-1)") (class "Default")
      (node (ref "R10") (pin "P2") (pinfunction "1_P2") (pintype "passive"))
      (node (ref "U6") (pin "P26") (pinfunction "RX2_P26") (pintype "input"))
    )
    (net (code "45") (name "Net-(R10C-1)") (class "Default")
      (node (ref "R10") (pin "P3") (pinfunction "1_P3") (pintype "passive"))
      (node (ref "U6") (pin "P23") (pinfunction "DIR_P23") (pintype "input"))
    )
    (net (code "46") (name "Net-(R10D-1)") (class "Default")
      (node (ref "R10") (pin "P4") (pinfunction "1_P4") (pintype "passive"))
      (node (ref "U6") (pin "P22") (pinfunction "WHEEL_TKS_P22") (pintype "input"))
    )
    (net (code "47") (name "Net-(R11A-1)") (class "Default")
      (node (ref "R11") (pin "P1") (pinfunction "1_P1") (pintype "passive"))
      (node (ref "U6") (pin "P20") (pinfunction "RTK_STAT_P20") (pintype "output"))
    )
    (net (code "48") (name "Net-(R11B-1)") (class "Default")
      (node (ref "R11") (pin "P2") (pinfunction "1_P2") (pintype "passive"))
      (node (ref "U6") (pin "P19") (pinfunction "GEO_FENCE_STAT_P19") (pintype "output"))
    )
    (net (code "49") (name "Net-(R19-Pad1)") (class "Default")
      (node (ref "R19") (pin "1") (pinfunction "1_1") (pintype "passive"))
      (node (ref "RTK") (pin "2") (pinfunction "2_2") (pintype "passive"))
    )
    (net (code "50") (name "Net-(U6-TIMEPULSE)") (class "Default")
      (node (ref "R12") (pin "1") (pinfunction "1_1") (pintype "passive"))
      (node (ref "U6") (pin "P53") (pinfunction "TIMEPULSE_P53") (pintype "output"))
    )
    (net (code "51") (name "PPS") (class "Default")
      (node (ref "D5") (pin "A") (pinfunction "A_A") (pintype "passive"))
      (node (ref "J6") (pin "1") (pinfunction "1_1") (pintype "passive"))
      (node (ref "R12") (pin "2") (pinfunction "2_2") (pintype "passive"))
    )
    (net (code "52") (name "RF_IN") (class "Default")
      (node (ref "D9") (pin "2") (pinfunction "2_2") (pintype "bidirectional"))
      (node (ref "E1") (pin "SIG") (pinfunction "SIGNAL_SIG") (pintype "bidirectional"))
      (node (ref "FB1") (pin "1") (pinfunction "1_1") (pintype "passive"))
      (node (ref "U6") (pin "P2") (pinfunction "RF_IN_P2") (pintype "input"))
    )
    (net (code "53") (name "RTK_STAT") (class "Default")
      (node (ref "R11") (pin "P8") (pinfunction "2_P8") (pintype "passive"))
      (node (ref "RTK") (pin "1") (pinfunction "1_1") (pintype "passive"))
    )
    (net (code "54") (name "RXI2") (class "Default")
      (node (ref "J7") (pin "3") (pinfunction "3_3") (pintype "passive"))
      (node (ref "R10") (pin "P7") (pinfunction "2_P7") (pintype "passive"))
    )
    (net (code "55") (name "RXI{slash}CIPO") (class "Default")
      (node (ref "J5") (pin "5") (pinfunction "5_5") (pintype "passive"))
      (node (ref "R9") (pin "P2") (pinfunction "1_P2") (pintype "passive"))
    )
    (net (code "56") (name "SCL{slash}CLK") (class "Default")
      (node (ref "J3") (pin "4") (pinfunction "4_4") (pintype "passive"))
      (node (ref "J4") (pin "4") (pinfunction "4_4") (pintype "passive"))
      (node (ref "J5") (pin "7") (pinfunction "7_7") (pintype "passive"))
      (node (ref "J6") (pin "6") (pinfunction "6_6") (pintype "passive"))
      (node (ref "R16") (pin "1") (pinfunction "1_1") (pintype "passive"))
      (node (ref "R9") (pin "P4") (pinfunction "1_P4") (pintype "passive"))
    )
    (net (code "57") (name "TXO2") (class "Default")
      (node (ref "J7") (pin "2") (pinfunction "2_2") (pintype "passive"))
      (node (ref "R10") (pin "P8") (pinfunction "2_P8") (pintype "passive"))
    )
    (net (code "58") (name "TXO{slash}COPI") (class "Default")
      (node (ref "J5") (pin "6") (pinfunction "6_6") (pintype "passive"))
      (node (ref "R9") (pin "P1") (pinfunction "1_P1") (pintype "passive"))
    )
    (net (code "59") (name "TX_READY") (class "Default")
      (node (ref "J6") (pin "5") (pinfunction "5_5") (pintype "passive"))
      (node (ref "R8") (pin "P1") (pinfunction "1_P1") (pintype "passive"))
    )
    (net (code "60") (name "VIN") (class "Default")
      (node (ref "C9") (pin "1") (pinfunction "1_1") (pintype "passive"))
      (node (ref "D3") (pin "5") (pinfunction "5_5") (pintype "power_in"))
      (node (ref "J2") (pin "VBUS1") (pinfunction "VBUS_VBUS1") (pintype "bidirectional"))
      (node (ref "J2") (pin "VBUS2") (pinfunction "VBUS_VBUS2") (pintype "bidirectional"))
      (node (ref "J5") (pin "2") (pinfunction "2_2") (pintype "passive"))
      (node (ref "U5") (pin "1") (pinfunction "IN_1") (pintype "input"))
      (node (ref "U5") (pin "3") (pinfunction "EN_3") (pintype "input"))
    )
    (net (code "61") (name "V_BATT") (class "Default")
      (node (ref "BT2") (pin "+") (pinfunction "+_+") (pintype "power_in"))
      (node (ref "C11") (pin "1") (pinfunction "1_1") (pintype "passive"))
      (node (ref "R24") (pin "1") (pinfunction "1_1") (pintype "passive"))
      (node (ref "TP1") (pin "1") (pinfunction "1_1") (pintype "bidirectional"))
      (node (ref "U6") (pin "P36") (pinfunction "V_BKCP_P36") (pintype "power_in"))
    )
    (net (code "62") (name "V_RF") (class "Default")
      (node (ref "R13") (pin "2") (pinfunction "2_2") (pintype "passive"))
      (node (ref "U6") (pin "P7") (pinfunction "V_RF_P7") (pintype "output"))
    )
    (net (code "63") (name "WT+") (class "Default")
      (node (ref "J5") (pin "11") (pinfunction "11_11") (pintype "passive"))
      (node (ref "R2") (pin "1") (pinfunction "1_1") (pintype "passive"))
    )
    (net (code "64") (name "WT_IN") (class "Default")
      (node (ref "R6") (pin "2") (pinfunction "2_2") (pintype "passive"))
      (node (ref "U1") (pin "1") (pinfunction "ANODE1_1") (pintype "input"))
    )
    (net (code "65") (name "WT_INV") (class "Default")
      (node (ref "R7") (pin "1") (pinfunction "1_1") (pintype "passive"))
      (node (ref "U1") (pin "7") (pinfunction "VOUT1_7") (pintype "output"))
      (node (ref "U3") (pin "P2") (pinfunction "A_P2") (pintype "input"))
    )
    (net (code "66") (name "WT_OUT") (class "Default")
      (node (ref "R10") (pin "P5") (pinfunction "2_P5") (pintype "passive"))
      (node (ref "U3") (pin "P4") (pinfunction "Y_P4") (pintype "output"))
    )
    (net (code "67") (name "unconnected-(J7-Pad1)") (class "Default")
      (node (ref "J7") (pin "1") (pinfunction "1_1") (pintype "passive"))
    )
    (net (code "68") (name "unconnected-(J7-Pad4)") (class "Default")
      (node (ref "J7") (pin "4") (pinfunction "4_4") (pintype "passive"))
    )
    (net (code "69") (name "unconnected-(J7-Pad5)") (class "Default")
      (node (ref "J7") (pin "5") (pinfunction "5_5") (pintype "passive"))
    )
    (net (code "70") (name "unconnected-(U6-ANT_DETECT-PadP4)") (class "Default")
      (node (ref "U6") (pin "P4") (pinfunction "ANT_DETECT_P4") (pintype "input"))
    )
    (net (code "71") (name "unconnected-(U6-ANT_OFF-PadP5)") (class "Default")
      (node (ref "U6") (pin "P5") (pinfunction "ANT_OFF_P5") (pintype "output"))
    )
    (net (code "72") (name "unconnected-(U6-~{ANT_SHORT}-PadP6)") (class "Default")
      (node (ref "U6") (pin "P6") (pinfunction "~{ANT_SHORT}_P6") (pintype "output"))
    )
  )
)
